# Pulse_Generator.net
KiCad netlist of a schematic drawn in Altium Designer
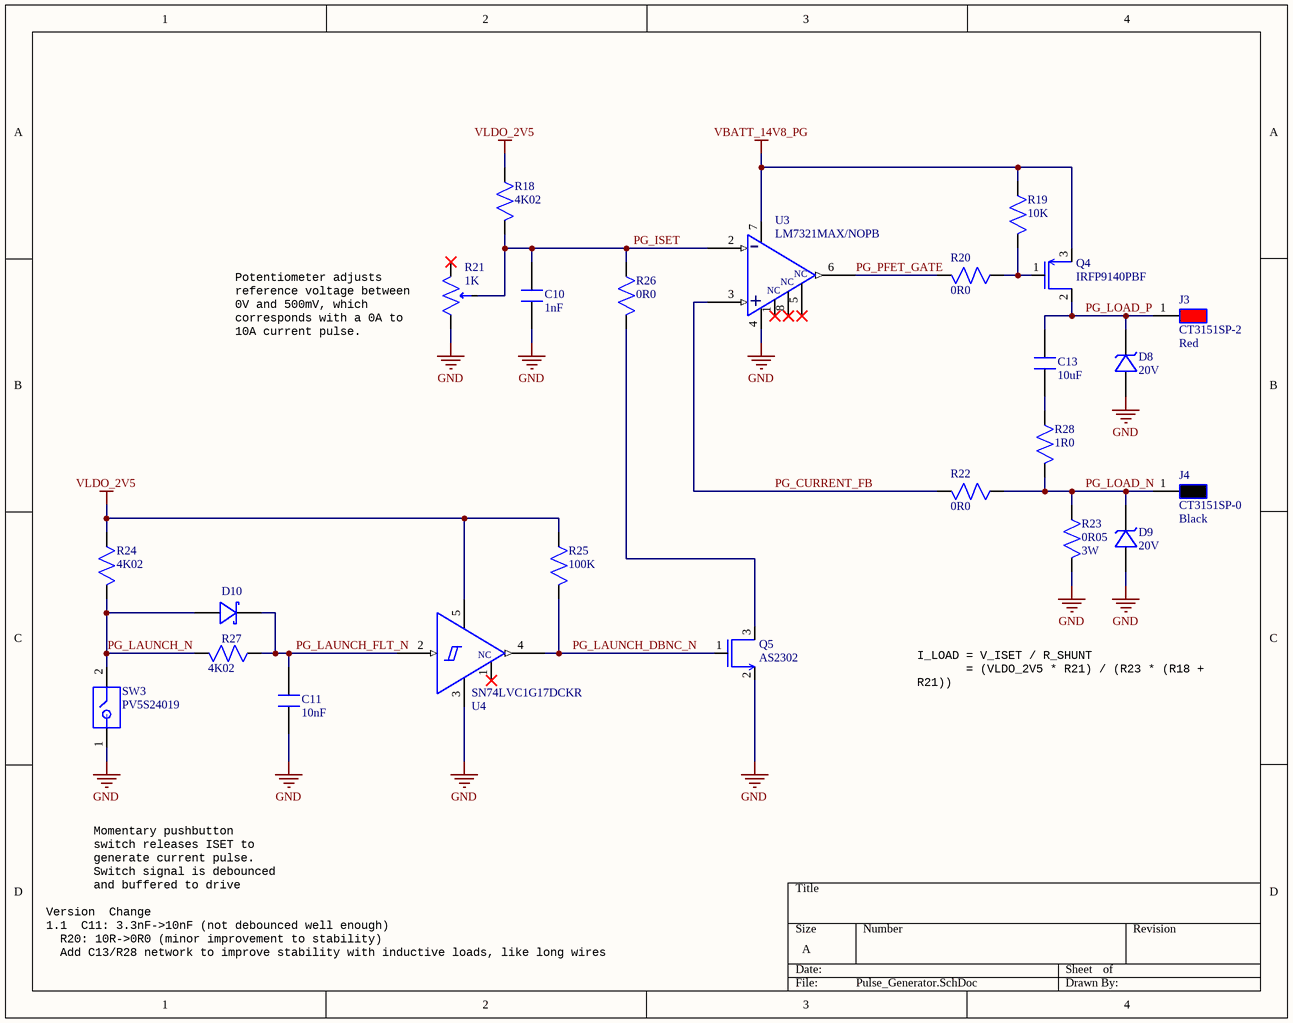
[diagram p0: Pulse_Generator.SchDoc]

(export (version "E")
  (design (tool "Eeschema 10.0.6"))
  (components
    (comp (ref "C10")
      (value "~")
      (footprint "0603_CAP")
      (fields
        (field (name "MANUFACTURER") "KYOCERA AVX")
        (field (name "PART NUMBER") "KGM15AR71H102KT")
        (field (name "TOLERANCE") "10%")
        (field (name "CAPACITANCE") "1nF")
      )
      (libsource (lib "SharedPartsLib") (part "CAP_0603_1nF"))
    )
    (comp (ref "C11")
      (value "CAP_0603_10nF")
      (footprint "0603_CAP")
      (fields
        (field (name "MANUFACTURER") "Samsung Electro-Mechanics")
        (field (name "PART NUMBER") "CL10B103KB8NNNC")
        (field (name "TOLERANCE") "10%")
        (field (name "CAPACITANCE") "10nF")
      )
      (libsource (lib "SharedPartsLib") (part "CAP_0603_10nF"))
    )
    (comp (ref "C13")
      (value "CAP_0805_10uF")
      (footprint "0805_CAP")
      (fields
        (field (name "MANUFACTURER") "Yageo")
        (field (name "PART NUMBER") "CC0805KKX5R5BB106")
        (field (name "TOLERANCE") "10%")
        (field (name "CAPACITANCE") "10uF")
      )
      (libsource (lib "SharedPartsLib") (part "CAP_0805_10uF"))
    )
    (comp (ref "D8")
      (value "*")
      (footprint "DO-214AC_SMA")
      (fields
        (field (name "MANUFACTURER") "Diodes Incorporated")
        (field (name "PART NUMBER") "SMAJ20AQ-13-F")
        (field (name "REVERSE STANDOFF VOLTAGE") "20V")
      )
      (libsource (lib "SharedPartsLib") (part "DIODE_TVS_20V_UNIDIR"))
    )
    (comp (ref "D9")
      (value "*")
      (footprint "DO-214AC_SMA")
      (fields
        (field (name "MANUFACTURER") "Diodes Incorporated")
        (field (name "PART NUMBER") "SMAJ20AQ-13-F")
        (field (name "REVERSE STANDOFF VOLTAGE") "20V")
      )
      (libsource (lib "SharedPartsLib") (part "DIODE_TVS_20V_UNIDIR"))
    )
    (comp (ref "D10")
      (value "*")
      (footprint "SOD-523")
      (fields (field (name "MANUFACTURER") "ON Semiconductor") (field (name "PART NUMBER") "RB520S30T5G"))
      (libsource (lib "SharedPartsLib") (part "DIODE_RB520S30T5G"))
    )
    (comp (ref "J3")
      (value "*")
      (footprint "CONN_BANANA_RED_CT3151SP-2")
      (fields
        (field (name "MANUFACTURER") "Cal Test Electronics")
        (field (name "PART NUMBER") "CT3151SP-2")
        (field (name "COLOUR") "Red")
      )
      (libsource (lib "SharedPartsLib") (part "CONN_BANANA_RED_CT3151SP-2"))
    )
    (comp (ref "J4")
      (value "*")
      (footprint "CONN_BANANA_BLK_CT3151SP-0")
      (fields
        (field (name "MANUFACTURER") "Cal Test Electronics")
        (field (name "PART NUMBER") "CT3151SP-0")
        (field (name "COLOUR") "Black")
      )
      (libsource (lib "SharedPartsLib") (part "CONN_BANANA_BLK_CT3151SP-2_1"))
    )
    (comp (ref "Q4")
      (value "*")
      (footprint "TO-247AC_NOHOLE")
      (fields (field (name "MANUFACTURER") "Vishay") (field (name "PART NUMBER") "IRFP9140PBF"))
      (libsource (lib "SharedPartsLib") (part "PFET_IRFP9140"))
    )
    (comp (ref "Q5")
      (value "*")
      (footprint "SOT-23-3")
      (fields
        (field (name "MANUFACTURER") "ANBON SEMICONDUCTOR (INT'L) LIMITED")
        (field (name "PART NUMBER") "AS2302")
      )
      (libsource (lib "SharedPartsLib") (part "NFET_AS2302"))
    )
    (comp (ref "R18")
      (value "~")
      (footprint "0603_RES")
      (fields
        (field (name "MANUFACTURER") "Stackpole Electronics Inc")
        (field (name "PART NUMBER") "RMCF0603FT4K02")
        (field (name "TOLERANCE") "1%")
        (field (name "RESISTANCE") "4K02")
      )
      (libsource (lib "SharedPartsLib") (part "RES_0603_4K02"))
    )
    (comp (ref "R19")
      (value "~")
      (footprint "0603_RES")
      (fields
        (field (name "MANUFACTURER") "Stackpole Electronics Inc")
        (field (name "PART NUMBER") "RMCF0603FT10K0")
        (field (name "TOLERANCE") "1%")
        (field (name "RESISTANCE") "10K")
      )
      (libsource (lib "SharedPartsLib") (part "RES_0603_10K"))
    )
    (comp (ref "R20")
      (value "~")
      (footprint "0603_RES")
      (fields (field (name "RESISTANCE") "0R0"))
      (libsource (lib "SharedPartsLib") (part "RES_0603_0R0"))
    )
    (comp (ref "R21")
      (value "~")
      (footprint "POT_PTV09A-4x15F-xxxx")
      (fields
        (field (name "MANUFACTURER") "Bourns Inc.")
        (field (name "PART NUMBER") "PTV09A-4015F-B102")
        (field (name "TOLERANCE") "20%")
        (field (name "RESISTANCE") "1K")
      )
      (libsource (lib "SharedPartsLib") (part "POT_1K_PTV09A-4015F-B102"))
    )
    (comp (ref "R22")
      (value "~")
      (footprint "0603_RES")
      (fields (field (name "RESISTANCE") "0R0"))
      (libsource (lib "SharedPartsLib") (part "RES_0603_0R0"))
    )
    (comp (ref "R23")
      (value "~")
      (footprint "RES_BR3FB50L0_0R05_1%")
      (fields
        (field (name "MANUFACTURER") "Stackpole Electronics")
        (field (name "PART NUMBER") "BR3FB50L0")
        (field (name "TOLERANCE") "1%")
        (field (name "RESISTANCE") "0R05")
        (field (name "POWER RATING") "3W")
      )
      (libsource (lib "SharedPartsLib") (part "RES_BR3FB50L0_0R05_1%"))
    )
    (comp (ref "R24")
      (value "~")
      (footprint "0603_RES")
      (fields
        (field (name "MANUFACTURER") "Stackpole Electronics Inc")
        (field (name "PART NUMBER") "RMCF0603FT4K02")
        (field (name "TOLERANCE") "1%")
        (field (name "RESISTANCE") "4K02")
      )
      (libsource (lib "SharedPartsLib") (part "RES_0603_4K02"))
    )
    (comp (ref "R25")
      (value "~")
      (footprint "0603_RES")
      (fields
        (field (name "MANUFACTURER") "Stackpole")
        (field (name "PART NUMBER") "RMCF0603FT100K")
        (field (name "TOLERANCE") "1%")
        (field (name "RESISTANCE") "100K")
      )
      (libsource (lib "SharedPartsLib") (part "RES_0603_100K"))
    )
    (comp (ref "R26")
      (value "~")
      (footprint "0603_RES")
      (fields (field (name "RESISTANCE") "0R0"))
      (libsource (lib "SharedPartsLib") (part "RES_0603_0R0"))
    )
    (comp (ref "R27")
      (value "~")
      (footprint "0603_RES")
      (fields
        (field (name "MANUFACTURER") "Stackpole Electronics Inc")
        (field (name "PART NUMBER") "RMCF0603FT4K02")
        (field (name "TOLERANCE") "1%")
        (field (name "RESISTANCE") "4K02")
      )
      (libsource (lib "SharedPartsLib") (part "RES_0603_4K02"))
    )
    (comp (ref "R28")
      (value "RES_0805_1R0")
      (footprint "0805_RES")
      (fields
        (field (name "MANUFACTURER") "Stackpole Electronics Inc")
        (field (name "PART NUMBER") "RMCF0805FT1R00")
        (field (name "TOLERANCE") "1%")
        (field (name "RESISTANCE") "1R0")
      )
      (libsource (lib "SharedPartsLib") (part "RES_0805_1R0"))
    )
    (comp (ref "SW3")
      (value "*")
      (footprint "SW_PUSHBUTTON_PV5S24019")
      (fields (field (name "MANUFACTURER") "E-Switch") (field (name "PART NUMBER") "PV5S24019"))
      (libsource (lib "SharedPartsLib") (part "SW_PUSHBUTTON_PV5S24019"))
    )
    (comp (ref "U3")
      (value "*")
      (footprint "SOIC-8_TI_PACKAGE_D")
      (fields (field (name "MANUFACTURER") "Texas Instruments") (field (name "PART NUMBER") "LM7321MAX/NOPB"))
      (libsource (lib "SharedPartsLib") (part "LM7321"))
    )
    (comp (ref "U4")
      (value "*")
      (footprint "SOT-353")
      (fields
        (field (name "MANUFACTURER") "Texas Instruments")
        (field (name "PART NUMBER") "SN74LVC1G17DCKR")
      )
      (libsource (lib "SharedPartsLib") (part "SN74LVC1G17"))
    )
  )
  (nets
    (net (code "1") (name "/PG_CURRENT_FB") (class "Default")
      (node (ref "R22") (pin "1") (pintype "passive"))
      (node (ref "U3") (pin "3") (pinfunction "IN+_3") (pintype "input"))
    )
    (net (code "2") (name "/PG_ISET") (class "Default")
      (node (ref "C10") (pin "2") (pintype "passive"))
      (node (ref "R18") (pin "1") (pintype "passive"))
      (node (ref "R21") (pin "2") (pintype "passive"))
      (node (ref "R26") (pin "2") (pintype "passive"))
      (node (ref "U3") (pin "2") (pinfunction "IN-_2") (pintype "input"))
    )
    (net (code "3") (name "/PG_LAUNCH_DBNC_N") (class "Default")
      (node (ref "Q5") (pin "1") (pinfunction "G_1") (pintype "passive"))
      (node (ref "R25") (pin "1") (pintype "passive"))
      (node (ref "U4") (pin "4") (pinfunction "Y_4") (pintype "output"))
    )
    (net (code "4") (name "/PG_LAUNCH_FLT_N") (class "Default")
      (node (ref "C11") (pin "2") (pintype "passive"))
      (node (ref "D10") (pin "1") (pintype "passive"))
      (node (ref "R27") (pin "2") (pintype "passive"))
      (node (ref "U4") (pin "2") (pinfunction "A_2") (pintype "input"))
    )
    (net (code "5") (name "/PG_LAUNCH_N") (class "Default")
      (node (ref "D10") (pin "2") (pintype "passive"))
      (node (ref "R24") (pin "1") (pintype "passive"))
      (node (ref "R27") (pin "1") (pintype "passive"))
      (node (ref "SW3") (pin "2") (pintype "passive"))
    )
    (net (code "6") (name "/PG_LOAD_N") (class "Default")
      (node (ref "D9") (pin "1") (pintype "passive"))
      (node (ref "J4") (pin "1") (pinfunction "1_1") (pintype "passive"))
      (node (ref "R22") (pin "2") (pintype "passive"))
      (node (ref "R23") (pin "2") (pintype "passive"))
      (node (ref "R28") (pin "1") (pintype "passive"))
    )
    (net (code "7") (name "/PG_LOAD_P") (class "Default")
      (node (ref "C13") (pin "2") (pintype "passive"))
      (node (ref "D8") (pin "1") (pintype "passive"))
      (node (ref "J3") (pin "1") (pinfunction "1_1") (pintype "passive"))
      (node (ref "Q4") (pin "2") (pinfunction "D_2") (pintype "passive"))
    )
    (net (code "8") (name "/PG_PFET_GATE") (class "Default")
      (node (ref "R20") (pin "1") (pintype "passive"))
      (node (ref "U3") (pin "6") (pinfunction "OUT_6") (pintype "output"))
    )
    (net (code "9") (name "GND") (class "Default")
      (node (ref "C10") (pin "1") (pintype "passive"))
      (node (ref "C11") (pin "1") (pintype "passive"))
      (node (ref "D8") (pin "2") (pintype "passive"))
      (node (ref "D9") (pin "2") (pintype "passive"))
      (node (ref "Q5") (pin "2") (pinfunction "S_2") (pintype "passive"))
      (node (ref "R21") (pin "1") (pintype "passive"))
      (node (ref "R23") (pin "1") (pintype "passive"))
      (node (ref "SW3") (pin "1") (pintype "passive"))
      (node (ref "U3") (pin "4") (pinfunction "V-_4") (pintype "passive"))
      (node (ref "U4") (pin "3") (pinfunction "GND_3") (pintype "passive"))
    )
    (net (code "10") (name "Net-(C13-Pad1)") (class "Default")
      (node (ref "C13") (pin "1") (pintype "passive"))
      (node (ref "R28") (pin "2") (pintype "passive"))
    )
    (net (code "11") (name "Net-(Q4-G)") (class "Default")
      (node (ref "Q4") (pin "1") (pinfunction "G_1") (pintype "passive"))
      (node (ref "R19") (pin "1") (pintype "passive"))
      (node (ref "R20") (pin "2") (pintype "passive"))
    )
    (net (code "12") (name "Net-(Q5-D)") (class "Default")
      (node (ref "Q5") (pin "3") (pinfunction "D_3") (pintype "passive"))
      (node (ref "R26") (pin "1") (pintype "passive"))
    )
    (net (code "13") (name "VBATT_14V8_PG") (class "Default")
      (node (ref "Q4") (pin "3") (pinfunction "S_3") (pintype "passive"))
      (node (ref "R19") (pin "2") (pintype "passive"))
      (node (ref "U3") (pin "7") (pinfunction "V+_7") (pintype "passive"))
    )
    (net (code "14") (name "VLDO_2V5") (class "Default")
      (node (ref "R18") (pin "2") (pintype "passive"))
      (node (ref "R24") (pin "2") (pintype "passive"))
      (node (ref "R25") (pin "2") (pintype "passive"))
      (node (ref "U4") (pin "5") (pinfunction "VCC_5") (pintype "passive"))
    )
    (net (code "15") (name "unconnected-(R21-Pad3)") (class "Default")
      (node (ref "R21") (pin "3") (pintype "passive+no_connect"))
    )
    (net (code "16") (name "unconnected-(U3-NC-Pad1)") (class "Default")
      (node (ref "U3") (pin "1") (pinfunction "NC_1") (pintype "passive+no_connect"))
    )
    (net (code "17") (name "unconnected-(U3-NC-Pad5)") (class "Default")
      (node (ref "U3") (pin "5") (pinfunction "NC_5") (pintype "passive+no_connect"))
    )
    (net (code "18") (name "unconnected-(U3-NC-Pad8)") (class "Default")
      (node (ref "U3") (pin "8") (pinfunction "NC_8") (pintype "passive+no_connect"))
    )
    (net (code "19") (name "unconnected-(U4-NC-Pad1)") (class "Default")
      (node (ref "U4") (pin "1") (pinfunction "NC_1") (pintype "passive+no_connect"))
    )
  )
)
